# unifying.net
KiCad netlist of a schematic drawn in Altium Designer
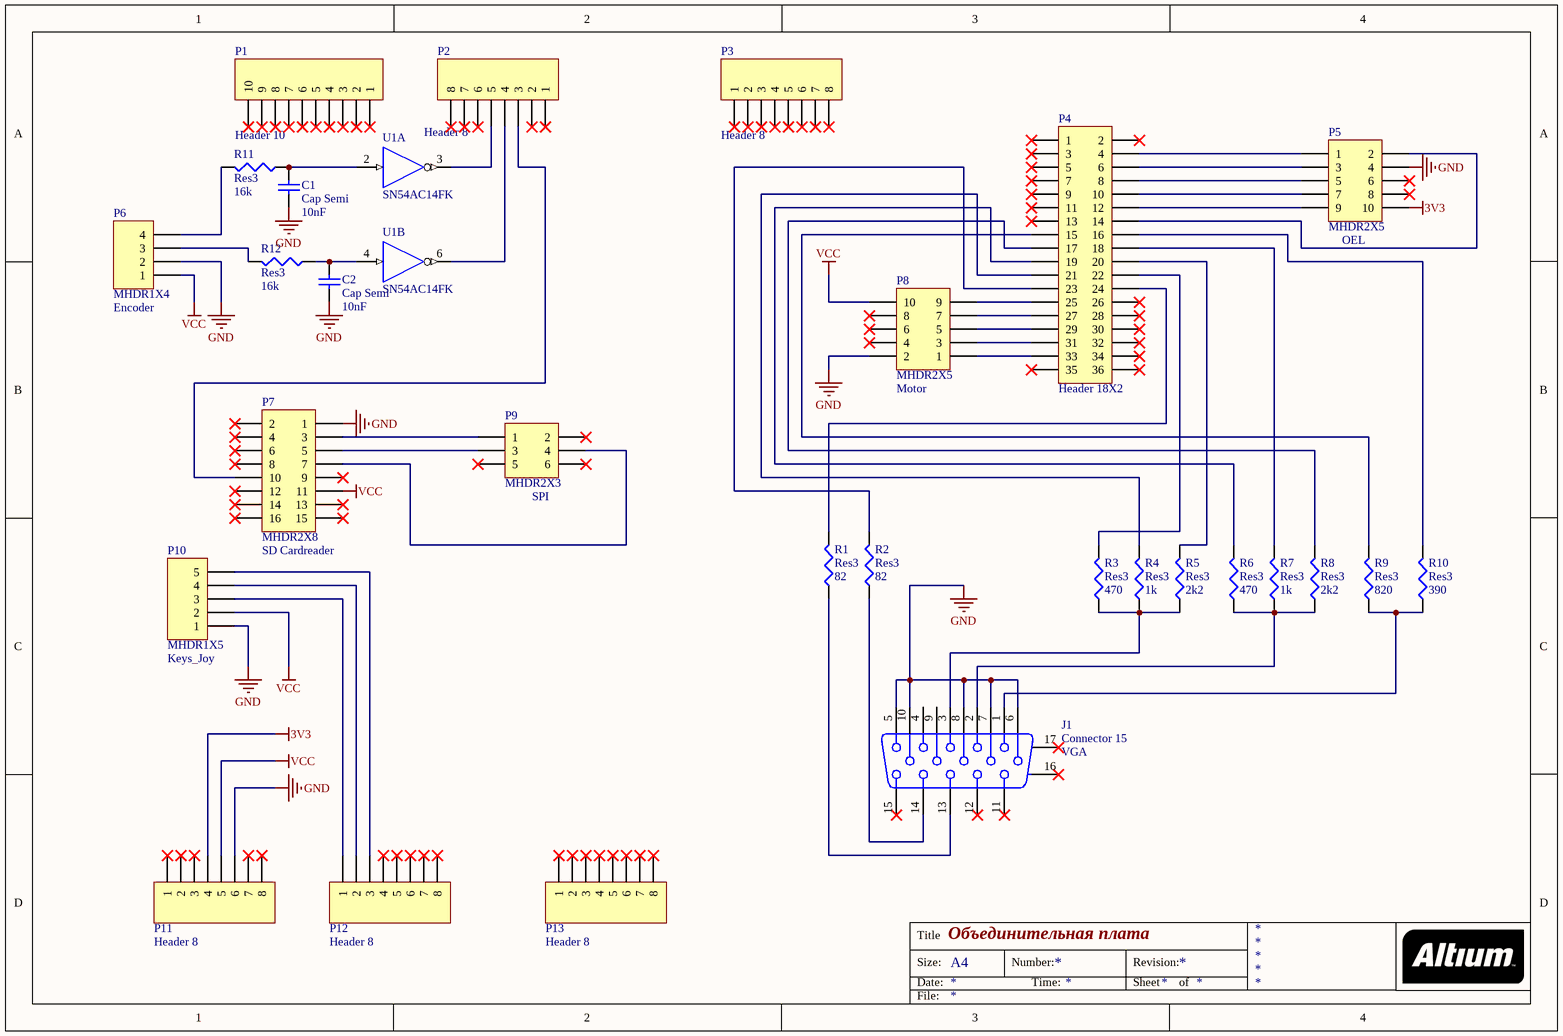
[diagram p0: unifying.SchDoc]

(export (version "E")
  (design (tool "Eeschema 10.0.6"))
  (components
    (comp (ref "C1")
      (value "Cap Semi")
      (footprint "C1206")
      (description "Capacitor (Semiconductor SIM Model)")
      (fields (field (name "ALTIUM_VALUE") "10nF") (field (name "PUBLISHER") "Altium Limited"))
      (libsource (lib "Miscellaneous Devices") (part "Cap Semi"))
    )
    (comp (ref "C2")
      (value "Cap Semi")
      (footprint "C1206")
      (description "Capacitor (Semiconductor SIM Model)")
      (fields (field (name "ALTIUM_VALUE") "10nF") (field (name "PUBLISHER") "Altium Limited"))
      (libsource (lib "Miscellaneous Devices") (part "Cap Semi"))
    )
    (comp (ref "J1")
      (value "Connector 15")
      (footprint "050DSUB0.762-4H15")
      (description "Receptacle Assembly, 15-Pin, Sim Line Connector")
      (fields (field (name "ALTIUM_UNNAMED_1") "VGA") (field (name "PUBLISHER") "Altium Limited"))
      (libsource (lib "Miscellaneous Connectors") (part "Connector 15"))
    )
    (comp (ref "P1")
      (value "Header 10")
      (footprint "HDR1X10")
      (description "Header, 10-Pin")
      (fields (field (name "PUBLISHER") "Altium Limited"))
      (libsource (lib "Miscellaneous Connectors") (part "Header 10"))
    )
    (comp (ref "P2")
      (value "Header 8")
      (footprint "HDR1X8")
      (description "Header, 8-Pin")
      (fields (field (name "PUBLISHER") "Altium Limited"))
      (libsource (lib "") (part "Header 8_2"))
    )
    (comp (ref "P3")
      (value "Header 8")
      (footprint "HDR1X8")
      (description "Header, 8-Pin")
      (fields (field (name "PUBLISHER") "Altium Limited"))
      (libsource (lib "") (part "Header 8_1"))
    )
    (comp (ref "P4")
      (value "Header 18X2")
      (footprint "HDR2X18")
      (description "Header, 18-Pin, Dual row")
      (fields (field (name "PUBLISHER") "Altium Limited"))
      (libsource (lib "Miscellaneous Connectors") (part "Header 18X2"))
    )
    (comp (ref "P5")
      (value "MHDR2X5")
      (footprint "MHDR2X5")
      (description "Header, 5-Pin, Dual row")
      (fields (field (name "ALTIUM_UNNAMED_1") "OEL") (field (name "PUBLISHER") "Altium Limited"))
      (libsource (lib "Miscellaneous Connectors") (part "MHDR2X5"))
    )
    (comp (ref "P6")
      (value "MHDR1X4")
      (footprint "MHDR1X4")
      (description "Header, 4-Pin")
      (fields (field (name "ALTIUM_UNNAMED_1") "Encoder") (field (name "PUBLISHER") "Altium Limited"))
      (libsource (lib "Miscellaneous Connectors") (part "MHDR1X4"))
    )
    (comp (ref "P7")
      (value "MHDR2X8")
      (footprint "MHDR2X8")
      (description "Header, 8-Pin, Dual row")
      (fields (field (name "ALTIUM_UNNAMED_1") "SD Cardreader") (field (name "PUBLISHER") "Altium Limited"))
      (libsource (lib "Miscellaneous Connectors") (part "MHDR2X8"))
    )
    (comp (ref "P8")
      (value "MHDR2X5")
      (footprint "MHDR2X5")
      (description "Header, 5-Pin, Dual row")
      (fields (field (name "ALTIUM_UNNAMED_1") "Motor") (field (name "PUBLISHER") "Altium Limited"))
      (libsource (lib "") (part "MHDR2X5_1"))
    )
    (comp (ref "P9")
      (value "MHDR2X3")
      (footprint "MHDR2X3")
      (description "Header, 3-Pin, Dual row")
      (fields (field (name "ALTIUM_UNNAMED_1") "SPI") (field (name "PUBLISHER") "Altium Limited"))
      (libsource (lib "Miscellaneous Connectors") (part "MHDR2X3"))
    )
    (comp (ref "P10")
      (value "MHDR1X5")
      (footprint "MHDR1X5")
      (description "Header, 5-Pin")
      (fields (field (name "ALTIUM_UNNAMED_1") "Keys_Joy") (field (name "PUBLISHER") "Altium Limited"))
      (libsource (lib "Miscellaneous Connectors") (part "MHDR1X5"))
    )
    (comp (ref "P11")
      (value "Header 8")
      (footprint "HDR1X8")
      (description "Header, 8-Pin")
      (fields (field (name "PUBLISHER") "Altium Limited"))
      (libsource (lib "Miscellaneous Connectors") (part "Header 8"))
    )
    (comp (ref "P12")
      (value "Header 8")
      (footprint "HDR1X8")
      (description "Header, 8-Pin")
      (fields (field (name "PUBLISHER") "Altium Limited"))
      (libsource (lib "Miscellaneous Connectors") (part "Header 8"))
    )
    (comp (ref "P13")
      (value "Header 8")
      (footprint "HDR1X8")
      (description "Header, 8-Pin")
      (fields (field (name "PUBLISHER") "Altium Limited"))
      (libsource (lib "Miscellaneous Connectors") (part "Header 8"))
    )
    (comp (ref "R1")
      (value "Res3")
      (footprint "J1-0603")
      (description "Resistor")
      (fields (field (name "ALTIUM_VALUE") "82") (field (name "PUBLISHER") "Altium Limited"))
      (libsource (lib "Miscellaneous Devices") (part "Res3"))
    )
    (comp (ref "R2")
      (value "Res3")
      (footprint "J1-0603")
      (description "Resistor")
      (fields (field (name "ALTIUM_VALUE") "82") (field (name "PUBLISHER") "Altium Limited"))
      (libsource (lib "Miscellaneous Devices") (part "Res3"))
    )
    (comp (ref "R3")
      (value "Res3")
      (footprint "J1-0603")
      (description "Resistor")
      (fields (field (name "ALTIUM_VALUE") "470") (field (name "PUBLISHER") "Altium Limited"))
      (libsource (lib "Miscellaneous Devices") (part "Res3"))
    )
    (comp (ref "R4")
      (value "Res3")
      (footprint "J1-0603")
      (description "Resistor")
      (fields (field (name "ALTIUM_VALUE") "1k") (field (name "PUBLISHER") "Altium Limited"))
      (libsource (lib "Miscellaneous Devices") (part "Res3"))
    )
    (comp (ref "R5")
      (value "Res3")
      (footprint "J1-0603")
      (description "Resistor")
      (fields (field (name "ALTIUM_VALUE") "2k2") (field (name "PUBLISHER") "Altium Limited"))
      (libsource (lib "Miscellaneous Devices") (part "Res3"))
    )
    (comp (ref "R6")
      (value "Res3")
      (footprint "J1-0603")
      (description "Resistor")
      (fields (field (name "ALTIUM_VALUE") "470") (field (name "PUBLISHER") "Altium Limited"))
      (libsource (lib "Miscellaneous Devices") (part "Res3"))
    )
    (comp (ref "R7")
      (value "Res3")
      (footprint "J1-0603")
      (description "Resistor")
      (fields (field (name "ALTIUM_VALUE") "1k") (field (name "PUBLISHER") "Altium Limited"))
      (libsource (lib "Miscellaneous Devices") (part "Res3"))
    )
    (comp (ref "R8")
      (value "Res3")
      (footprint "J1-0603")
      (description "Resistor")
      (fields (field (name "ALTIUM_VALUE") "2k2") (field (name "PUBLISHER") "Altium Limited"))
      (libsource (lib "Miscellaneous Devices") (part "Res3"))
    )
    (comp (ref "R9")
      (value "Res3")
      (footprint "J1-0603")
      (description "Resistor")
      (fields (field (name "ALTIUM_VALUE") "820") (field (name "PUBLISHER") "Altium Limited"))
      (libsource (lib "Miscellaneous Devices") (part "Res3"))
    )
    (comp (ref "R10")
      (value "Res3")
      (footprint "J1-0603")
      (description "Resistor")
      (fields (field (name "ALTIUM_VALUE") "390") (field (name "PUBLISHER") "Altium Limited"))
      (libsource (lib "Miscellaneous Devices") (part "Res3"))
    )
    (comp (ref "R11")
      (value "Res3")
      (footprint "J1-0603")
      (description "Resistor")
      (fields (field (name "ALTIUM_VALUE") "16k") (field (name "PUBLISHER") "Altium Limited"))
      (libsource (lib "Miscellaneous Devices") (part "Res3"))
    )
    (comp (ref "R12")
      (value "Res3")
      (footprint "J1-0603")
      (description "Resistor")
      (fields (field (name "ALTIUM_VALUE") "16k") (field (name "PUBLISHER") "Altium Limited"))
      (libsource (lib "Miscellaneous Devices") (part "Res3"))
    )
    (comp (ref "U1")
      (value "SN54AC14FK")
      (footprint "FK020")
      (description "Hex Schmitt-Trigger Inverter")
      (fields (field (name "PUBLISHER") "Altium Limited"))
      (libsource (lib "TI Logic Gate 1") (part "SN54AC14FK"))
    )
  )
  (nets
    (net (code "1") (name "3V3") (class "Default")
      (node (ref "P11") (pin "4") (pinfunction "4_4") (pintype "passive"))
      (node (ref "P5") (pin "10") (pinfunction "10_10") (pintype "passive"))
    )
    (net (code "2") (name "GND") (class "Default")
      (node (ref "C1") (pin "1") (pinfunction "1_1") (pintype "passive"))
      (node (ref "C2") (pin "1") (pinfunction "1_1") (pintype "passive"))
      (node (ref "J1") (pin "10") (pinfunction "10_10") (pintype "passive"))
      (node (ref "J1") (pin "5") (pinfunction "5_5") (pintype "passive"))
      (node (ref "J1") (pin "6") (pinfunction "6_6") (pintype "passive"))
      (node (ref "J1") (pin "7") (pinfunction "7_7") (pintype "passive"))
      (node (ref "J1") (pin "8") (pinfunction "8_8") (pintype "passive"))
      (node (ref "P10") (pin "1") (pinfunction "1_1") (pintype "passive"))
      (node (ref "P11") (pin "6") (pinfunction "6_6") (pintype "passive"))
      (node (ref "P5") (pin "4") (pinfunction "4_4") (pintype "passive"))
      (node (ref "P6") (pin "2") (pinfunction "2_2") (pintype "passive"))
      (node (ref "P7") (pin "1") (pinfunction "1_1") (pintype "passive"))
      (node (ref "P8") (pin "2") (pinfunction "2_2") (pintype "passive"))
      (node (ref "U1") (pin "10") (pinfunction "GND_10") (pintype "power_in"))
    )
    (net (code "3") (name "Net-(J1-Pad1)") (class "Default")
      (node (ref "J1") (pin "1") (pinfunction "1_1") (pintype "passive"))
      (node (ref "R10") (pin "1") (pinfunction "1_1") (pintype "passive"))
      (node (ref "R9") (pin "1") (pinfunction "1_1") (pintype "passive"))
    )
    (net (code "4") (name "Net-(J1-Pad2)") (class "Default")
      (node (ref "J1") (pin "2") (pinfunction "2_2") (pintype "passive"))
      (node (ref "R6") (pin "1") (pinfunction "1_1") (pintype "passive"))
      (node (ref "R7") (pin "1") (pinfunction "1_1") (pintype "passive"))
      (node (ref "R8") (pin "1") (pinfunction "1_1") (pintype "passive"))
    )
    (net (code "5") (name "Net-(J1-Pad3)") (class "Default")
      (node (ref "J1") (pin "3") (pinfunction "3_3") (pintype "passive"))
      (node (ref "R3") (pin "1") (pinfunction "1_1") (pintype "passive"))
      (node (ref "R4") (pin "1") (pinfunction "1_1") (pintype "passive"))
      (node (ref "R5") (pin "1") (pinfunction "1_1") (pintype "passive"))
    )
    (net (code "6") (name "Net-(J1-Pad13)") (class "Default")
      (node (ref "J1") (pin "13") (pinfunction "13_13") (pintype "passive"))
      (node (ref "R1") (pin "1") (pinfunction "1_1") (pintype "passive"))
    )
    (net (code "7") (name "Net-(J1-Pad14)") (class "Default")
      (node (ref "J1") (pin "14") (pinfunction "14_14") (pintype "passive"))
      (node (ref "R2") (pin "1") (pinfunction "1_1") (pintype "passive"))
    )
    (net (code "8") (name "Net-(P2-Pad3)") (class "Default")
      (node (ref "P2") (pin "3") (pinfunction "3_3") (pintype "passive"))
      (node (ref "P7") (pin "10") (pinfunction "10_10") (pintype "passive"))
    )
    (net (code "9") (name "Net-(P4-Pad4)") (class "Default")
      (node (ref "P4") (pin "4") (pinfunction "4_4") (pintype "passive"))
      (node (ref "P5") (pin "1") (pinfunction "1_1") (pintype "passive"))
    )
    (net (code "10") (name "Net-(P4-Pad6)") (class "Default")
      (node (ref "P4") (pin "6") (pinfunction "6_6") (pintype "passive"))
      (node (ref "P5") (pin "3") (pinfunction "3_3") (pintype "passive"))
    )
    (net (code "11") (name "Net-(P4-Pad8)") (class "Default")
      (node (ref "P4") (pin "8") (pinfunction "8_8") (pintype "passive"))
      (node (ref "P5") (pin "5") (pinfunction "5_5") (pintype "passive"))
    )
    (net (code "12") (name "Net-(P4-Pad10)") (class "Default")
      (node (ref "P4") (pin "10") (pinfunction "10_10") (pintype "passive"))
      (node (ref "P5") (pin "7") (pinfunction "7_7") (pintype "passive"))
    )
    (net (code "13") (name "Net-(P4-Pad12)") (class "Default")
      (node (ref "P4") (pin "12") (pinfunction "12_12") (pintype "passive"))
      (node (ref "P5") (pin "9") (pinfunction "9_9") (pintype "passive"))
    )
    (net (code "14") (name "Net-(P4-Pad14)") (class "Default")
      (node (ref "P4") (pin "14") (pinfunction "14_14") (pintype "passive"))
      (node (ref "P5") (pin "2") (pinfunction "2_2") (pintype "passive"))
    )
    (net (code "15") (name "Net-(P4-Pad15)") (class "Default")
      (node (ref "P4") (pin "15") (pinfunction "15_15") (pintype "passive"))
      (node (ref "R9") (pin "2") (pinfunction "2_2") (pintype "passive"))
    )
    (net (code "16") (name "Net-(P4-Pad16)") (class "Default")
      (node (ref "P4") (pin "16") (pinfunction "16_16") (pintype "passive"))
      (node (ref "R10") (pin "2") (pinfunction "2_2") (pintype "passive"))
    )
    (net (code "17") (name "Net-(P4-Pad17)") (class "Default")
      (node (ref "P4") (pin "17") (pinfunction "17_17") (pintype "passive"))
      (node (ref "R8") (pin "2") (pinfunction "2_2") (pintype "passive"))
    )
    (net (code "18") (name "Net-(P4-Pad18)") (class "Default")
      (node (ref "P4") (pin "18") (pinfunction "18_18") (pintype "passive"))
      (node (ref "R7") (pin "2") (pinfunction "2_2") (pintype "passive"))
    )
    (net (code "19") (name "Net-(P4-Pad19)") (class "Default")
      (node (ref "P4") (pin "19") (pinfunction "19_19") (pintype "passive"))
      (node (ref "R6") (pin "2") (pinfunction "2_2") (pintype "passive"))
    )
    (net (code "20") (name "Net-(P4-Pad20)") (class "Default")
      (node (ref "P4") (pin "20") (pinfunction "20_20") (pintype "passive"))
      (node (ref "R5") (pin "2") (pinfunction "2_2") (pintype "passive"))
    )
    (net (code "21") (name "Net-(P4-Pad21)") (class "Default")
      (node (ref "P4") (pin "21") (pinfunction "21_21") (pintype "passive"))
      (node (ref "R4") (pin "2") (pinfunction "2_2") (pintype "passive"))
    )
    (net (code "22") (name "Net-(P4-Pad22)") (class "Default")
      (node (ref "P4") (pin "22") (pinfunction "22_22") (pintype "passive"))
      (node (ref "R3") (pin "2") (pinfunction "2_2") (pintype "passive"))
    )
    (net (code "23") (name "Net-(P4-Pad23)") (class "Default")
      (node (ref "P4") (pin "23") (pinfunction "23_23") (pintype "passive"))
      (node (ref "R2") (pin "2") (pinfunction "2_2") (pintype "passive"))
    )
    (net (code "24") (name "Net-(P4-Pad24)") (class "Default")
      (node (ref "P4") (pin "24") (pinfunction "24_24") (pintype "passive"))
      (node (ref "R1") (pin "2") (pinfunction "2_2") (pintype "passive"))
    )
    (net (code "25") (name "Net-(P4-Pad25)") (class "Default")
      (node (ref "P4") (pin "25") (pinfunction "25_25") (pintype "passive"))
      (node (ref "P8") (pin "9") (pinfunction "9_9") (pintype "passive"))
    )
    (net (code "26") (name "Net-(P4-Pad27)") (class "Default")
      (node (ref "P4") (pin "27") (pinfunction "27_27") (pintype "passive"))
      (node (ref "P8") (pin "7") (pinfunction "7_7") (pintype "passive"))
    )
    (net (code "27") (name "Net-(P4-Pad29)") (class "Default")
      (node (ref "P4") (pin "29") (pinfunction "29_29") (pintype "passive"))
      (node (ref "P8") (pin "5") (pinfunction "5_5") (pintype "passive"))
    )
    (net (code "28") (name "Net-(P4-Pad31)") (class "Default")
      (node (ref "P4") (pin "31") (pinfunction "31_31") (pintype "passive"))
      (node (ref "P8") (pin "3") (pinfunction "3_3") (pintype "passive"))
    )
    (net (code "29") (name "Net-(P4-Pad33)") (class "Default")
      (node (ref "P4") (pin "33") (pinfunction "33_33") (pintype "passive"))
      (node (ref "P8") (pin "1") (pinfunction "1_1") (pintype "passive"))
    )
    (net (code "30") (name "Net-(P6-Pad3)") (class "Default")
      (node (ref "P6") (pin "3") (pinfunction "3_3") (pintype "passive"))
      (node (ref "R12") (pin "2") (pinfunction "2_2") (pintype "passive"))
    )
    (net (code "31") (name "Net-(P6-Pad4)") (class "Default")
      (node (ref "P6") (pin "4") (pinfunction "4_4") (pintype "passive"))
      (node (ref "R11") (pin "2") (pinfunction "2_2") (pintype "passive"))
    )
    (net (code "32") (name "Net-(P7-Pad3)") (class "Default")
      (node (ref "P7") (pin "3") (pinfunction "3_3") (pintype "passive"))
      (node (ref "P9") (pin "1") (pinfunction "1_1") (pintype "passive"))
    )
    (net (code "33") (name "Net-(P7-Pad5)") (class "Default")
      (node (ref "P7") (pin "5") (pinfunction "5_5") (pintype "passive"))
      (node (ref "P9") (pin "3") (pinfunction "3_3") (pintype "passive"))
    )
    (net (code "34") (name "Net-(P7-Pad7)") (class "Default")
      (node (ref "P7") (pin "7") (pinfunction "7_7") (pintype "passive"))
      (node (ref "P9") (pin "4") (pinfunction "4_4") (pintype "passive"))
    )
    (net (code "35") (name "Net-(P10-Pad3)") (class "Default")
      (node (ref "P10") (pin "3") (pinfunction "3_3") (pintype "passive"))
      (node (ref "P12") (pin "1") (pinfunction "1_1") (pintype "passive"))
    )
    (net (code "36") (name "Net-(P10-Pad4)") (class "Default")
      (node (ref "P10") (pin "4") (pinfunction "4_4") (pintype "passive"))
      (node (ref "P12") (pin "2") (pinfunction "2_2") (pintype "passive"))
    )
    (net (code "37") (name "Net-(P10-Pad5)") (class "Default")
      (node (ref "P10") (pin "5") (pinfunction "5_5") (pintype "passive"))
      (node (ref "P12") (pin "3") (pinfunction "3_3") (pintype "passive"))
    )
    (net (code "38") (name "Net-(U1A-A)") (class "Default")
      (node (ref "C1") (pin "2") (pinfunction "2_2") (pintype "passive"))
      (node (ref "R11") (pin "1") (pinfunction "1_1") (pintype "passive"))
      (node (ref "U1") (pin "2") (pinfunction "A_2") (pintype "input"))
    )
    (net (code "39") (name "Net-(U1A-Y)") (class "Default")
      (node (ref "P2") (pin "5") (pinfunction "5_5") (pintype "passive"))
      (node (ref "U1") (pin "3") (pinfunction "Y_3") (pintype "output"))
    )
    (net (code "40") (name "Net-(U1B-A)") (class "Default")
      (node (ref "C2") (pin "2") (pinfunction "2_2") (pintype "passive"))
      (node (ref "R12") (pin "1") (pinfunction "1_1") (pintype "passive"))
      (node (ref "U1") (pin "4") (pinfunction "A_4") (pintype "input"))
    )
    (net (code "41") (name "Net-(U1B-Y)") (class "Default")
      (node (ref "P2") (pin "4") (pinfunction "4_4") (pintype "passive"))
      (node (ref "U1") (pin "6") (pinfunction "Y_6") (pintype "output"))
    )
    (net (code "42") (name "VCC") (class "Default")
      (node (ref "P10") (pin "2") (pinfunction "2_2") (pintype "passive"))
      (node (ref "P11") (pin "5") (pinfunction "5_5") (pintype "passive"))
      (node (ref "P6") (pin "1") (pinfunction "1_1") (pintype "passive"))
      (node (ref "P7") (pin "11") (pinfunction "11_11") (pintype "passive"))
      (node (ref "P8") (pin "10") (pinfunction "10_10") (pintype "passive"))
      (node (ref "U1") (pin "20") (pinfunction "VCC_20") (pintype "power_in"))
    )
    (net (code "43") (name "unconnected-(J1-MH1-Pad16)") (class "Default")
      (node (ref "J1") (pin "16") (pinfunction "MH1_16") (pintype "passive+no_connect"))
    )
    (net (code "44") (name "unconnected-(J1-MH2-Pad17)") (class "Default")
      (node (ref "J1") (pin "17") (pinfunction "MH2_17") (pintype "passive+no_connect"))
    )
    (net (code "45") (name "unconnected-(J1-Pad4)") (class "Default")
      (node (ref "J1") (pin "4") (pinfunction "4_4") (pintype "passive"))
    )
    (net (code "46") (name "unconnected-(J1-Pad9)") (class "Default")
      (node (ref "J1") (pin "9") (pinfunction "9_9") (pintype "passive"))
    )
    (net (code "47") (name "unconnected-(J1-Pad11)") (class "Default")
      (node (ref "J1") (pin "11") (pinfunction "11_11") (pintype "passive+no_connect"))
    )
    (net (code "48") (name "unconnected-(J1-Pad12)") (class "Default")
      (node (ref "J1") (pin "12") (pinfunction "12_12") (pintype "passive+no_connect"))
    )
    (net (code "49") (name "unconnected-(J1-Pad15)") (class "Default")
      (node (ref "J1") (pin "15") (pinfunction "15_15") (pintype "passive+no_connect"))
    )
    (net (code "50") (name "unconnected-(P1-Pad1)") (class "Default")
      (node (ref "P1") (pin "1") (pinfunction "1_1") (pintype "passive+no_connect"))
    )
    (net (code "51") (name "unconnected-(P1-Pad2)") (class "Default")
      (node (ref "P1") (pin "2") (pinfunction "2_2") (pintype "passive+no_connect"))
    )
    (net (code "52") (name "unconnected-(P1-Pad3)") (class "Default")
      (node (ref "P1") (pin "3") (pinfunction "3_3") (pintype "passive+no_connect"))
    )
    (net (code "53") (name "unconnected-(P1-Pad4)") (class "Default")
      (node (ref "P1") (pin "4") (pinfunction "4_4") (pintype "passive+no_connect"))
    )
    (net (code "54") (name "unconnected-(P1-Pad5)") (class "Default")
      (node (ref "P1") (pin "5") (pinfunction "5_5") (pintype "passive+no_connect"))
    )
    (net (code "55") (name "unconnected-(P1-Pad6)") (class "Default")
      (node (ref "P1") (pin "6") (pinfunction "6_6") (pintype "passive+no_connect"))
    )
    (net (code "56") (name "unconnected-(P1-Pad7)") (class "Default")
      (node (ref "P1") (pin "7") (pinfunction "7_7") (pintype "passive+no_connect"))
    )
    (net (code "57") (name "unconnected-(P1-Pad8)") (class "Default")
      (node (ref "P1") (pin "8") (pinfunction "8_8") (pintype "passive+no_connect"))
    )
    (net (code "58") (name "unconnected-(P1-Pad9)") (class "Default")
      (node (ref "P1") (pin "9") (pinfunction "9_9") (pintype "passive+no_connect"))
    )
    (net (code "59") (name "unconnected-(P1-Pad10)") (class "Default")
      (node (ref "P1") (pin "10") (pinfunction "10_10") (pintype "passive+no_connect"))
    )
    (net (code "60") (name "unconnected-(P2-Pad1)") (class "Default")
      (node (ref "P2") (pin "1") (pinfunction "1_1") (pintype "passive+no_connect"))
    )
    (net (code "61") (name "unconnected-(P2-Pad2)") (class "Default")
      (node (ref "P2") (pin "2") (pinfunction "2_2") (pintype "passive+no_connect"))
    )
    (net (code "62") (name "unconnected-(P2-Pad6)") (class "Default")
      (node (ref "P2") (pin "6") (pinfunction "6_6") (pintype "passive+no_connect"))
    )
    (net (code "63") (name "unconnected-(P2-Pad7)") (class "Default")
      (node (ref "P2") (pin "7") (pinfunction "7_7") (pintype "passive+no_connect"))
    )
    (net (code "64") (name "unconnected-(P2-Pad8)") (class "Default")
      (node (ref "P2") (pin "8") (pinfunction "8_8") (pintype "passive+no_connect"))
    )
    (net (code "65") (name "unconnected-(P3-Pad1)") (class "Default")
      (node (ref "P3") (pin "1") (pinfunction "1_1") (pintype "passive+no_connect"))
    )
    (net (code "66") (name "unconnected-(P3-Pad2)") (class "Default")
      (node (ref "P3") (pin "2") (pinfunction "2_2") (pintype "passive+no_connect"))
    )
    (net (code "67") (name "unconnected-(P3-Pad3)") (class "Default")
      (node (ref "P3") (pin "3") (pinfunction "3_3") (pintype "passive+no_connect"))
    )
    (net (code "68") (name "unconnected-(P3-Pad4)") (class "Default")
      (node (ref "P3") (pin "4") (pinfunction "4_4") (pintype "passive+no_connect"))
    )
    (net (code "69") (name "unconnected-(P3-Pad5)") (class "Default")
      (node (ref "P3") (pin "5") (pinfunction "5_5") (pintype "passive+no_connect"))
    )
    (net (code "70") (name "unconnected-(P3-Pad6)") (class "Default")
      (node (ref "P3") (pin "6") (pinfunction "6_6") (pintype "passive+no_connect"))
    )
    (net (code "71") (name "unconnected-(P3-Pad7)") (class "Default")
      (node (ref "P3") (pin "7") (pinfunction "7_7") (pintype "passive+no_connect"))
    )
    (net (code "72") (name "unconnected-(P3-Pad8)") (class "Default")
      (node (ref "P3") (pin "8") (pinfunction "8_8") (pintype "passive+no_connect"))
    )
    (net (code "73") (name "unconnected-(P4-Pad1)") (class "Default")
      (node (ref "P4") (pin "1") (pinfunction "1_1") (pintype "passive+no_connect"))
    )
    (net (code "74") (name "unconnected-(P4-Pad2)") (class "Default")
      (node (ref "P4") (pin "2") (pinfunction "2_2") (pintype "passive+no_connect"))
    )
    (net (code "75") (name "unconnected-(P4-Pad3)") (class "Default")
      (node (ref "P4") (pin "3") (pinfunction "3_3") (pintype "passive+no_connect"))
    )
    (net (code "76") (name "unconnected-(P4-Pad5)") (class "Default")
      (node (ref "P4") (pin "5") (pinfunction "5_5") (pintype "passive+no_connect"))
    )
    (net (code "77") (name "unconnected-(P4-Pad7)") (class "Default")
      (node (ref "P4") (pin "7") (pinfunction "7_7") (pintype "passive+no_connect"))
    )
    (net (code "78") (name "unconnected-(P4-Pad9)") (class "Default")
      (node (ref "P4") (pin "9") (pinfunction "9_9") (pintype "passive+no_connect"))
    )
    (net (code "79") (name "unconnected-(P4-Pad11)") (class "Default")
      (node (ref "P4") (pin "11") (pinfunction "11_11") (pintype "passive+no_connect"))
    )
    (net (code "80") (name "unconnected-(P4-Pad13)") (class "Default")
      (node (ref "P4") (pin "13") (pinfunction "13_13") (pintype "passive+no_connect"))
    )
    (net (code "81") (name "unconnected-(P4-Pad26)") (class "Default")
      (node (ref "P4") (pin "26") (pinfunction "26_26") (pintype "passive+no_connect"))
    )
    (net (code "82") (name "unconnected-(P4-Pad28)") (class "Default")
      (node (ref "P4") (pin "28") (pinfunction "28_28") (pintype "passive+no_connect"))
    )
    (net (code "83") (name "unconnected-(P4-Pad30)") (class "Default")
      (node (ref "P4") (pin "30") (pinfunction "30_30") (pintype "passive+no_connect"))
    )
    (net (code "84") (name "unconnected-(P4-Pad32)") (class "Default")
      (node (ref "P4") (pin "32") (pinfunction "32_32") (pintype "passive+no_connect"))
    )
    (net (code "85") (name "unconnected-(P4-Pad34)") (class "Default")
      (node (ref "P4") (pin "34") (pinfunction "34_34") (pintype "passive+no_connect"))
    )
    (net (code "86") (name "unconnected-(P4-Pad35)") (class "Default")
      (node (ref "P4") (pin "35") (pinfunction "35_35") (pintype "passive+no_connect"))
    )
    (net (code "87") (name "unconnected-(P4-Pad36)") (class "Default")
      (node (ref "P4") (pin "36") (pinfunction "36_36") (pintype "passive+no_connect"))
    )
    (net (code "88") (name "unconnected-(P5-Pad6)") (class "Default")
      (node (ref "P5") (pin "6") (pinfunction "6_6") (pintype "passive+no_connect"))
    )
    (net (code "89") (name "unconnected-(P5-Pad8)") (class "Default")
      (node (ref "P5") (pin "8") (pinfunction "8_8") (pintype "passive+no_connect"))
    )
    (net (code "90") (name "unconnected-(P7-Pad2)") (class "Default")
      (node (ref "P7") (pin "2") (pinfunction "2_2") (pintype "passive+no_connect"))
    )
    (net (code "91") (name "unconnected-(P7-Pad4)") (class "Default")
      (node (ref "P7") (pin "4") (pinfunction "4_4") (pintype "passive+no_connect"))
    )
    (net (code "92") (name "unconnected-(P7-Pad6)") (class "Default")
      (node (ref "P7") (pin "6") (pinfunction "6_6") (pintype "passive+no_connect"))
    )
    (net (code "93") (name "unconnected-(P7-Pad8)") (class "Default")
      (node (ref "P7") (pin "8") (pinfunction "8_8") (pintype "passive+no_connect"))
    )
    (net (code "94") (name "unconnected-(P7-Pad9)") (class "Default")
      (node (ref "P7") (pin "9") (pinfunction "9_9") (pintype "passive+no_connect"))
    )
    (net (code "95") (name "unconnected-(P7-Pad12)") (class "Default")
      (node (ref "P7") (pin "12") (pinfunction "12_12") (pintype "passive+no_connect"))
    )
    (net (code "96") (name "unconnected-(P7-Pad13)") (class "Default")
      (node (ref "P7") (pin "13") (pinfunction "13_13") (pintype "passive+no_connect"))
    )
    (net (code "97") (name "unconnected-(P7-Pad14)") (class "Default")
      (node (ref "P7") (pin "14") (pinfunction "14_14") (pintype "passive+no_connect"))
    )
    (net (code "98") (name "unconnected-(P7-Pad15)") (class "Default")
      (node (ref "P7") (pin "15") (pinfunction "15_15") (pintype "passive+no_connect"))
    )
    (net (code "99") (name "unconnected-(P7-Pad16)") (class "Default")
      (node (ref "P7") (pin "16") (pinfunction "16_16") (pintype "passive+no_connect"))
    )
    (net (code "100") (name "unconnected-(P8-Pad4)") (class "Default")
      (node (ref "P8") (pin "4") (pinfunction "4_4") (pintype "passive+no_connect"))
    )
    (net (code "101") (name "unconnected-(P8-Pad6)") (class "Default")
      (node (ref "P8") (pin "6") (pinfunction "6_6") (pintype "passive+no_connect"))
    )
    (net (code "102") (name "unconnected-(P8-Pad8)") (class "Default")
      (node (ref "P8") (pin "8") (pinfunction "8_8") (pintype "passive+no_connect"))
    )
    (net (code "103") (name "unconnected-(P9-Pad2)") (class "Default")
      (node (ref "P9") (pin "2") (pinfunction "2_2") (pintype "passive+no_connect"))
    )
    (net (code "104") (name "unconnected-(P9-Pad5)") (class "Default")
      (node (ref "P9") (pin "5") (pinfunction "5_5") (pintype "passive+no_connect"))
    )
    (net (code "105") (name "unconnected-(P9-Pad6)") (class "Default")
      (node (ref "P9") (pin "6") (pinfunction "6_6") (pintype "passive+no_connect"))
    )
    (net (code "106") (name "unconnected-(P11-Pad1)") (class "Default")
      (node (ref "P11") (pin "1") (pinfunction "1_1") (pintype "passive+no_connect"))
    )
    (net (code "107") (name "unconnected-(P11-Pad2)") (class "Default")
      (node (ref "P11") (pin "2") (pinfunction "2_2") (pintype "passive+no_connect"))
    )
    (net (code "108") (name "unconnected-(P11-Pad3)") (class "Default")
      (node (ref "P11") (pin "3") (pinfunction "3_3") (pintype "passive+no_connect"))
    )
    (net (code "109") (name "unconnected-(P11-Pad7)") (class "Default")
      (node (ref "P11") (pin "7") (pinfunction "7_7") (pintype "passive+no_connect"))
    )
    (net (code "110") (name "unconnected-(P11-Pad8)") (class "Default")
      (node (ref "P11") (pin "8") (pinfunction "8_8") (pintype "passive+no_connect"))
    )
    (net (code "111") (name "unconnected-(P12-Pad4)") (class "Default")
      (node (ref "P12") (pin "4") (pinfunction "4_4") (pintype "passive+no_connect"))
    )
    (net (code "112") (name "unconnected-(P12-Pad5)") (class "Default")
      (node (ref "P12") (pin "5") (pinfunction "5_5") (pintype "passive+no_connect"))
    )
    (net (code "113") (name "unconnected-(P12-Pad6)") (class "Default")
      (node (ref "P12") (pin "6") (pinfunction "6_6") (pintype "passive+no_connect"))
    )
    (net (code "114") (name "unconnected-(P12-Pad7)") (class "Default")
      (node (ref "P12") (pin "7") (pinfunction "7_7") (pintype "passive+no_connect"))
    )
    (net (code "115") (name "unconnected-(P12-Pad8)") (class "Default")
      (node (ref "P12") (pin "8") (pinfunction "8_8") (pintype "passive+no_connect"))
    )
    (net (code "116") (name "unconnected-(P13-Pad1)") (class "Default")
      (node (ref "P13") (pin "1") (pinfunction "1_1") (pintype "passive+no_connect"))
    )
    (net (code "117") (name "unconnected-(P13-Pad2)") (class "Default")
      (node (ref "P13") (pin "2") (pinfunction "2_2") (pintype "passive+no_connect"))
    )
    (net (code "118") (name "unconnected-(P13-Pad3)") (class "Default")
      (node (ref "P13") (pin "3") (pinfunction "3_3") (pintype "passive+no_connect"))
    )
    (net (code "119") (name "unconnected-(P13-Pad4)") (class "Default")
      (node (ref "P13") (pin "4") (pinfunction "4_4") (pintype "passive+no_connect"))
    )
    (net (code "120") (name "unconnected-(P13-Pad5)") (class "Default")
      (node (ref "P13") (pin "5") (pinfunction "5_5") (pintype "passive+no_connect"))
    )
    (net (code "121") (name "unconnected-(P13-Pad6)") (class "Default")
      (node (ref "P13") (pin "6") (pinfunction "6_6") (pintype "passive+no_connect"))
    )
    (net (code "122") (name "unconnected-(P13-Pad7)") (class "Default")
      (node (ref "P13") (pin "7") (pinfunction "7_7") (pintype "passive+no_connect"))
    )
    (net (code "123") (name "unconnected-(P13-Pad8)") (class "Default")
      (node (ref "P13") (pin "8") (pinfunction "8_8") (pintype "passive+no_connect"))
    )
  )
)
